# 467444_130_3_4.net
KiCad netlist of a schematic drawn in Altium Designer
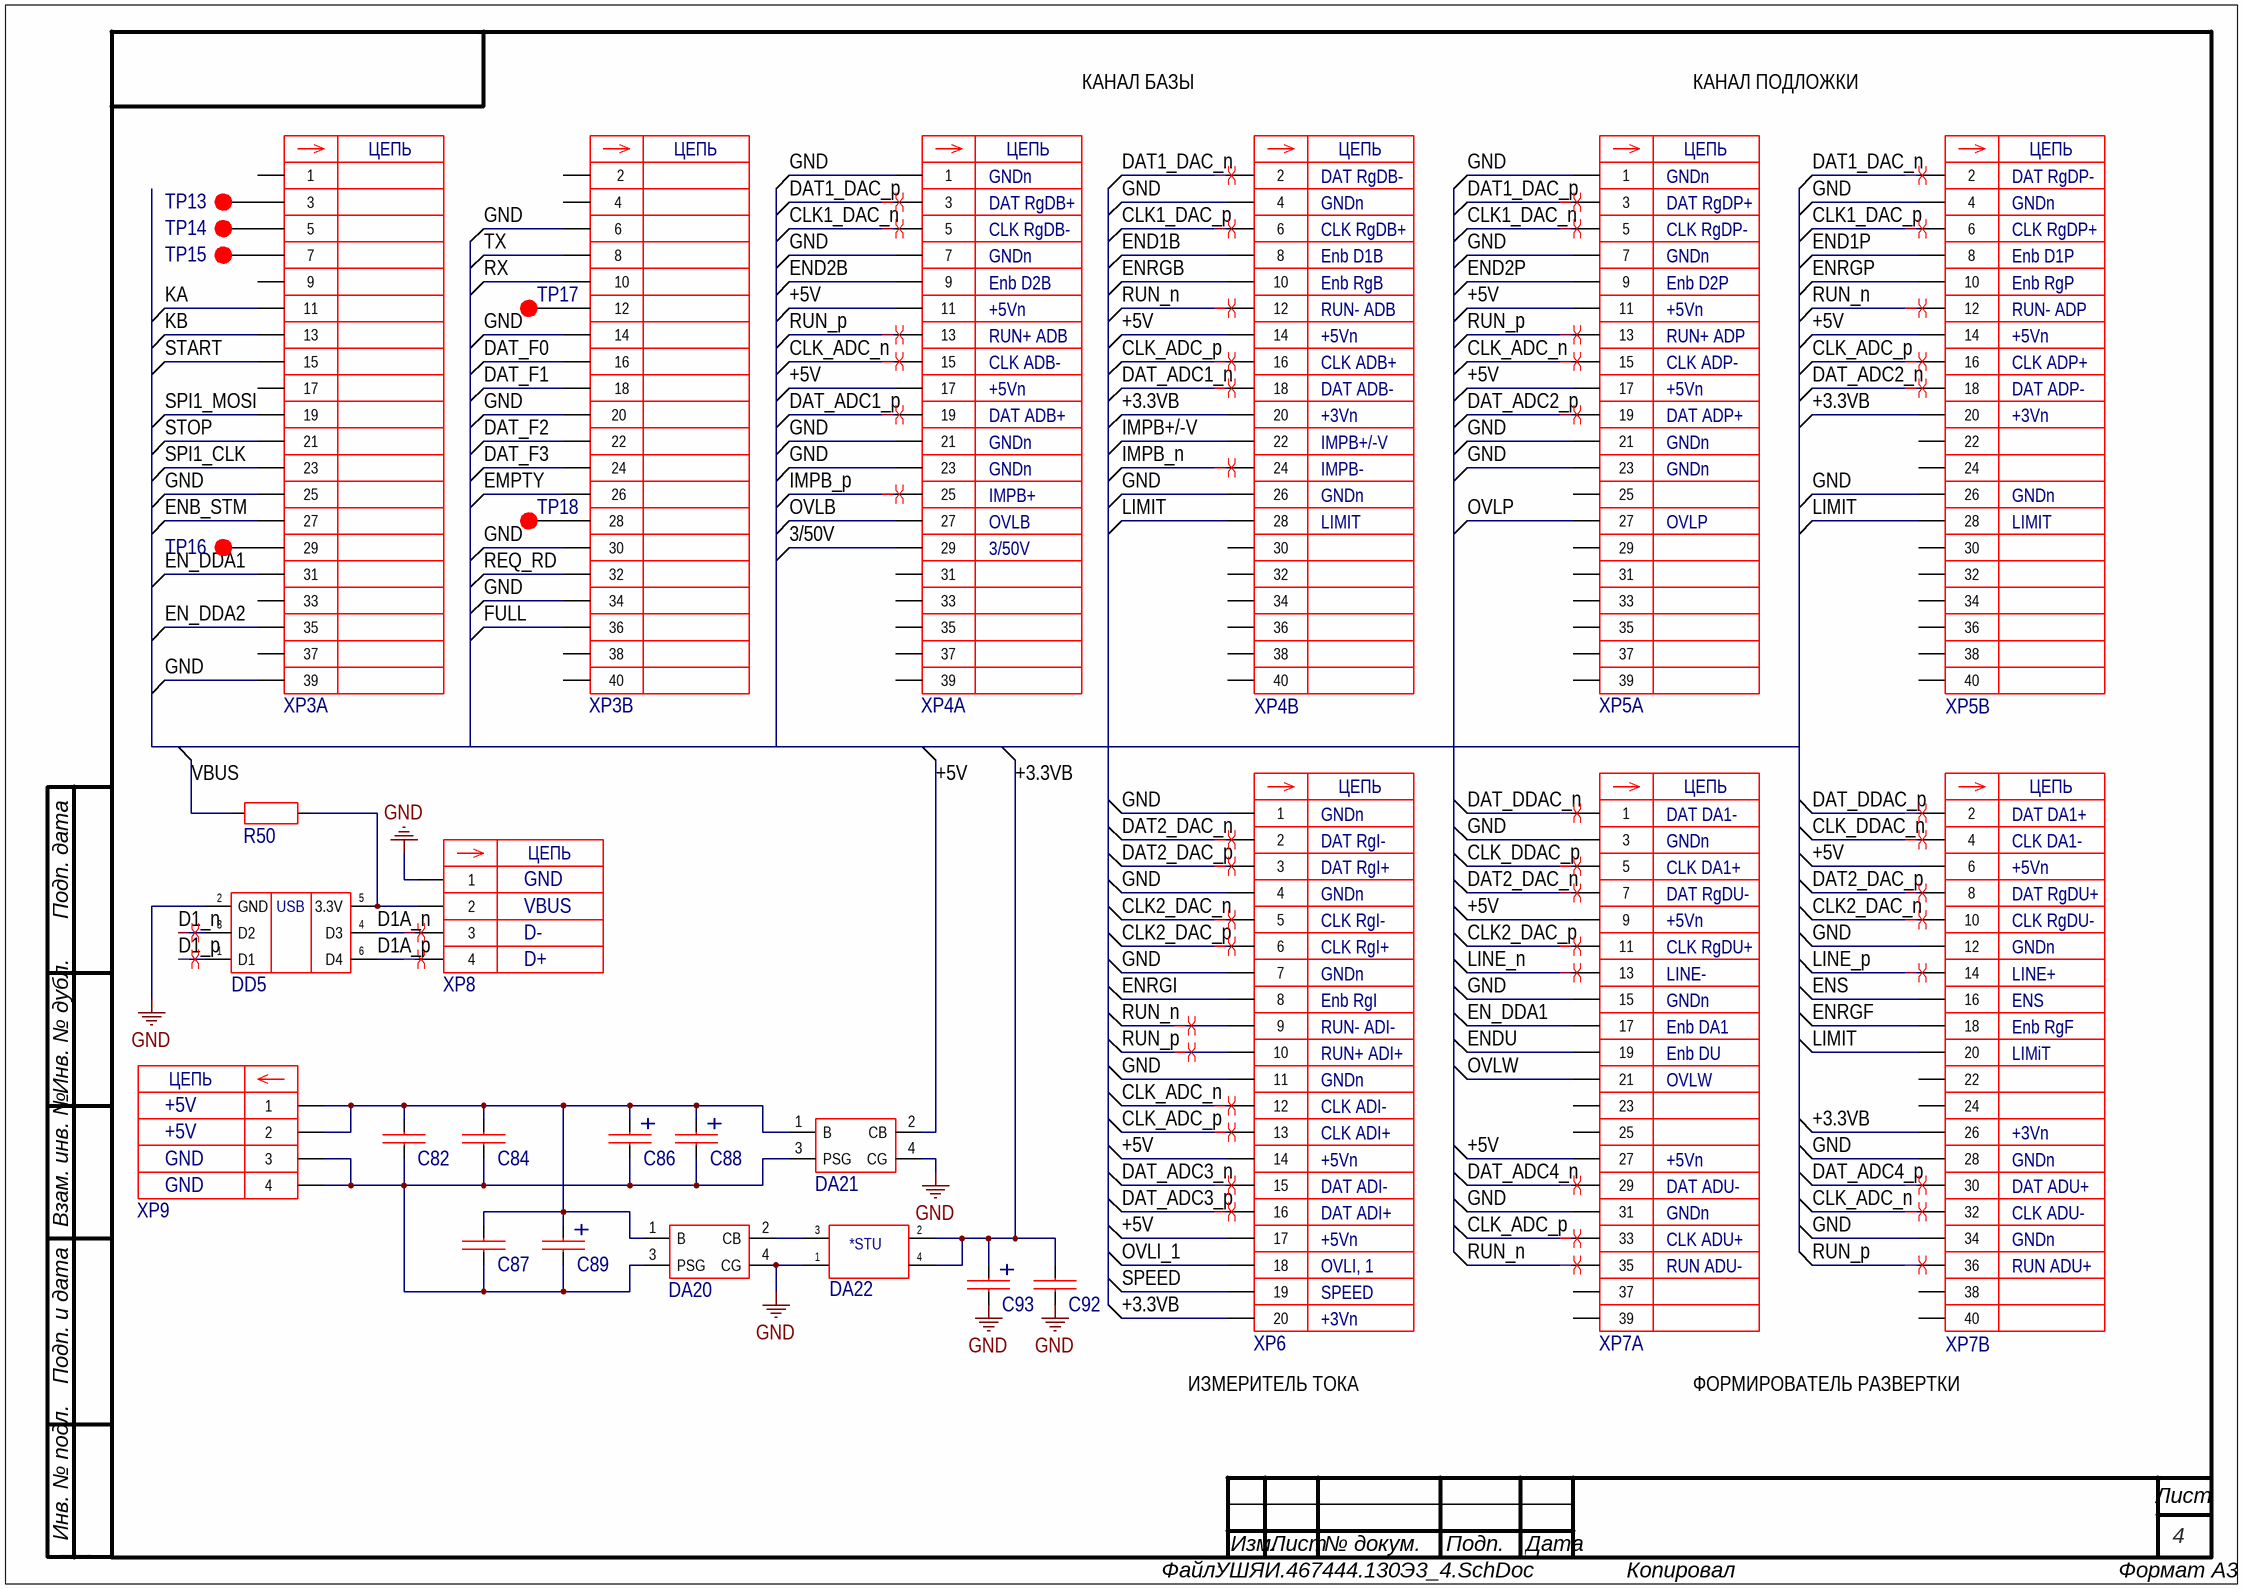
[diagram p0: УШЯИ.467444.130Э3_4.SchDoc]

(export (version "E")
  (design (tool "Eeschema 10.0.6"))
  (components
    (comp (ref "C82")
      (value "0,1 µF")
      (footprint "C_0805 [2012 Metric]")
      (description "Неполярный конденсатор")
      (fields (field (name "MANUFACTURER") "Murata") (field (name "VOLTAGE") "50V"))
      (libsource (lib "lib") (part "C_const"))
    )
    (comp (ref "C84")
      (value "0,1 µF")
      (footprint "C_0805 [2012 Metric]")
      (description "Неполярный конденсатор")
      (fields (field (name "MANUFACTURER") "Murata") (field (name "VOLTAGE") "50V"))
      (libsource (lib "lib") (part "C_const"))
    )
    (comp (ref "C86")
      (value "1000 µF")
      (footprint "С_EXR_10x21")
      (description "Полярный конденсатор")
      (fields (field (name "MANUFACTURER") "Hitano") (field (name "VOLTAGE") "16V"))
      (libsource (lib "lib") (part "C_electrolytic"))
    )
    (comp (ref "C87")
      (value "0,1 µF")
      (footprint "C_0805 [2012 Metric]")
      (description "Неполярный конденсатор")
      (fields (field (name "MANUFACTURER") "Murata") (field (name "VOLTAGE") "50V"))
      (libsource (lib "lib") (part "C_const"))
    )
    (comp (ref "C88")
      (value "10 µF")
      (footprint "C+_1210 [3528-21 Metric]")
      (description "Полярный конденсатор")
      (fields (field (name "MANUFACTURER") "KYOCERA AVX") (field (name "VOLTAGE") "20V\r\n10V"))
      (libsource (lib "lib") (part "C_electrolytic"))
    )
    (comp (ref "C89")
      (value "10 µF")
      (footprint "C+_1210 [3528-21 Metric]")
      (description "Полярный конденсатор")
      (fields (field (name "MANUFACTURER") "KYOCERA AVX") (field (name "VOLTAGE") "20V\r\n10V"))
      (libsource (lib "lib") (part "C_electrolytic"))
    )
    (comp (ref "C92")
      (value "0,1 µF")
      (footprint "C_0805 [2012 Metric]")
      (description "Неполярный конденсатор")
      (fields (field (name "MANUFACTURER") "Murata") (field (name "VOLTAGE") "50V"))
      (libsource (lib "lib") (part "C_const"))
    )
    (comp (ref "C93")
      (value "10 µF")
      (footprint "C+_1210 [3528-21 Metric]")
      (description "Полярный конденсатор")
      (fields (field (name "MANUFACTURER") "KYOCERA AVX") (field (name "VOLTAGE") "20V\r\n10V"))
      (libsource (lib "lib") (part "C_electrolytic"))
    )
    (comp (ref "DA20")
      (value "BNX028-01")
      (footprint "F_BNX028-01")
      (description "16В, 35дБ")
      (fields (field (name "MANUFACTURER") "Murata Electronics"))
      (libsource (lib "lib") (part "F_BNX022-01"))
    )
    (comp (ref "DA21")
      (value "BNX028-01")
      (footprint "F_BNX028-01")
      (description "16В, 35дБ")
      (fields (field (name "MANUFACTURER") "Murata Electronics"))
      (libsource (lib "lib") (part "F_BNX022-01"))
    )
    (comp (ref "DA22")
      (value "LD1117AS33TR")
      (footprint "SOT-223")
      (description "IC, Fixed LDO Voltage Regulator, 5.3V to 10V, 1.15V Dropout, 3.3Vout, 1Aout")
      (fields (field (name "MANUFACTURER") "STMicroelectronics"))
      (libsource (lib "lib") (part "VolReg_LD1117AS33TR"))
    )
    (comp (ref "DD5")
      (value "USBUF01W6")
      (footprint "SOT-323-6")
      (description "EMI Filter, 2-Channel, USB Upstream Terminator, ESD Protection")
      (fields (field (name "MANUFACTURER") "STMicroelectronics"))
      (libsource (lib "lib") (part "USBUF01W6"))
    )
    (comp (ref "R50")
      (value "30R")
      (footprint "R_0805 [2012 Metric]")
      (fields (field (name "TOLERANCE") "±5%"))
      (libsource (lib "lib") (part "R_Const"))
    )
    (comp (ref "TP13") (value "~") (footprint "DSP_1.3") (libsource (lib "lib") (part "TP")))
    (comp (ref "TP14") (value "~") (footprint "DSP_1.3") (libsource (lib "lib") (part "TP")))
    (comp (ref "TP15") (value "~") (footprint "DSP_1.3") (libsource (lib "lib") (part "TP")))
    (comp (ref "TP16") (value "~") (footprint "DSP_1.3") (libsource (lib "lib") (part "TP")))
    (comp (ref "TP17") (value "~") (footprint "DSP_1.3") (libsource (lib "lib") (part "TP")))
    (comp (ref "TP18") (value "~") (footprint "DSP_1.3") (libsource (lib "lib") (part "TP")))
    (comp (ref "XP3")
      (value "BH-40")
      (footprint "BH-40")
      (description "Male, 40 pins, 2 rows, Vertical")
      (fields (field (name "MANUFACTURER") "Connfly electronic"))
      (libsource (lib "lib") (part "M_40"))
    )
    (comp (ref "XP4")
      (value "BH2-40")
      (footprint "BH2-40")
      (description "Male, 40 pins, 2 rows, Vertical, DS1014-40, 2 mm")
      (fields (field (name "MANUFACTURER") "Connfly electronic"))
      (libsource (lib "lib") (part "M_40"))
    )
    (comp (ref "XP5")
      (value "BH2-40")
      (footprint "BH2-40")
      (description "Male, 40 pins, 2 rows, Vertical, DS1014-40, 2 mm")
      (fields (field (name "MANUFACTURER") "Connfly electronic"))
      (libsource (lib "lib") (part "M_40"))
    )
    (comp (ref "XP6")
      (value "BH2-20R")
      (footprint "BH2-20R")
      (description "Male, 20 pins, 2 rows, Right Angle, DS1014-20RF1B-B, 2 mm")
      (fields (field (name "MANUFACTURER") "Connfly electronic"))
      (libsource (lib "lib") (part "M_20"))
    )
    (comp (ref "XP7")
      (value "BH2-40")
      (footprint "BH2-40")
      (description "Male, 40 pins, 2 rows, Vertical, DS1014-40, 2 mm")
      (fields (field (name "MANUFACTURER") "Connfly electronic"))
      (libsource (lib "lib") (part "M_40"))
    )
    (comp (ref "XP8")
      (value "AMPMODU II 280371-2")
      (footprint "AMP II-280371-2")
      (description "Male, 4 pin, 1 row, Vertical, Board-to-Board, 2.54 mm")
      (fields (field (name "MANUFACTURER") "TE Connectivity"))
      (libsource (lib "") (part "M_4_1"))
    )
    (comp (ref "XP9")
      (value "AMPMODU II 280371-2")
      (footprint "AMP II-280371-2")
      (description "Male, 4 pin, 1 row, Vertical, Board-to-Board, 2.54 mm")
      (fields (field (name "MANUFACTURER") "TE Connectivity"))
      (libsource (lib "lib") (part "M_4"))
    )
  )
  (nets
    (net (code "1") (name "/+3.3VB") (class "Default")
      (node (ref "C92") (pin "2") (pinfunction "2_2") (pintype "passive"))
      (node (ref "C93") (pin "+") (pinfunction "+_+") (pintype "passive"))
      (node (ref "DA22") (pin "2") (pinfunction "VOUT_2") (pintype "passive"))
      (node (ref "DA22") (pin "4") (pinfunction "VOUT_4") (pintype "passive"))
      (node (ref "XP4") (pin "20") (pinfunction "20_20") (pintype "passive"))
      (node (ref "XP5") (pin "20") (pinfunction "20_20") (pintype "passive"))
      (node (ref "XP6") (pin "20") (pinfunction "20_20") (pintype "passive"))
      (node (ref "XP7") (pin "26") (pinfunction "26_26") (pintype "passive"))
    )
    (net (code "2") (name "/+5V") (class "Default")
      (node (ref "DA21") (pin "2") (pinfunction "CB_2") (pintype "passive"))
      (node (ref "XP4") (pin "11") (pinfunction "11_11") (pintype "passive"))
      (node (ref "XP4") (pin "14") (pinfunction "14_14") (pintype "passive"))
      (node (ref "XP4") (pin "17") (pinfunction "17_17") (pintype "passive"))
      (node (ref "XP5") (pin "11") (pinfunction "11_11") (pintype "passive"))
      (node (ref "XP5") (pin "14") (pinfunction "14_14") (pintype "passive"))
      (node (ref "XP5") (pin "17") (pinfunction "17_17") (pintype "passive"))
      (node (ref "XP6") (pin "14") (pinfunction "14_14") (pintype "passive"))
      (node (ref "XP6") (pin "17") (pinfunction "17_17") (pintype "passive"))
      (node (ref "XP7") (pin "27") (pinfunction "27_27") (pintype "passive"))
      (node (ref "XP7") (pin "6") (pinfunction "6_6") (pintype "passive"))
      (node (ref "XP7") (pin "9") (pinfunction "9_9") (pintype "passive"))
    )
    (net (code "3") (name "/3{slash}50V") (class "Default")
      (node (ref "XP4") (pin "29") (pinfunction "29_29") (pintype "passive"))
    )
    (net (code "4") (name "/CLK1_DAC_n") (class "Default")
      (node (ref "XP4") (pin "5") (pinfunction "5_5") (pintype "passive"))
      (node (ref "XP5") (pin "5") (pinfunction "5_5") (pintype "passive"))
    )
    (net (code "5") (name "/CLK1_DAC_p") (class "Default")
      (node (ref "XP4") (pin "6") (pinfunction "6_6") (pintype "passive"))
      (node (ref "XP5") (pin "6") (pinfunction "6_6") (pintype "passive"))
    )
    (net (code "6") (name "/CLK2_DAC_n") (class "Default")
      (node (ref "XP6") (pin "5") (pinfunction "5_5") (pintype "passive"))
      (node (ref "XP7") (pin "10") (pinfunction "10_10") (pintype "passive"))
    )
    (net (code "7") (name "/CLK2_DAC_p") (class "Default")
      (node (ref "XP6") (pin "6") (pinfunction "6_6") (pintype "passive"))
      (node (ref "XP7") (pin "11") (pinfunction "11_11") (pintype "passive"))
    )
    (net (code "8") (name "/CLK_ADC_n") (class "Default")
      (node (ref "XP4") (pin "15") (pinfunction "15_15") (pintype "passive"))
      (node (ref "XP5") (pin "15") (pinfunction "15_15") (pintype "passive"))
      (node (ref "XP6") (pin "12") (pinfunction "12_12") (pintype "passive"))
      (node (ref "XP7") (pin "32") (pinfunction "32_32") (pintype "passive"))
    )
    (net (code "9") (name "/CLK_ADC_p") (class "Default")
      (node (ref "XP4") (pin "16") (pinfunction "16_16") (pintype "passive"))
      (node (ref "XP5") (pin "16") (pinfunction "16_16") (pintype "passive"))
      (node (ref "XP6") (pin "13") (pinfunction "13_13") (pintype "passive"))
      (node (ref "XP7") (pin "33") (pinfunction "33_33") (pintype "passive"))
    )
    (net (code "10") (name "/CLK_DDAC_n") (class "Default")
      (node (ref "XP7") (pin "4") (pinfunction "4_4") (pintype "passive"))
    )
    (net (code "11") (name "/CLK_DDAC_p") (class "Default")
      (node (ref "XP7") (pin "5") (pinfunction "5_5") (pintype "passive"))
    )
    (net (code "12") (name "/D1A_n") (class "Default")
      (node (ref "DD5") (pin "4") (pinfunction "D3_4") (pintype "passive"))
      (node (ref "XP8") (pin "3") (pinfunction "3_3") (pintype "passive"))
    )
    (net (code "13") (name "/D1A_p") (class "Default")
      (node (ref "DD5") (pin "6") (pinfunction "D4_6") (pintype "passive"))
      (node (ref "XP8") (pin "4") (pinfunction "4_4") (pintype "passive"))
    )
    (net (code "14") (name "/D1_n") (class "Default")
      (node (ref "DD5") (pin "3") (pinfunction "D2_3") (pintype "passive"))
    )
    (net (code "15") (name "/D1_p") (class "Default")
      (node (ref "DD5") (pin "1") (pinfunction "D1_1") (pintype "passive"))
    )
    (net (code "16") (name "/DAT1_DAC_n") (class "Default")
      (node (ref "XP4") (pin "2") (pinfunction "2_2") (pintype "passive"))
      (node (ref "XP5") (pin "2") (pinfunction "2_2") (pintype "passive"))
    )
    (net (code "17") (name "/DAT1_DAC_p") (class "Default")
      (node (ref "XP4") (pin "3") (pinfunction "3_3") (pintype "passive"))
      (node (ref "XP5") (pin "3") (pinfunction "3_3") (pintype "passive"))
    )
    (net (code "18") (name "/DAT2_DAC_n") (class "Default")
      (node (ref "XP6") (pin "2") (pinfunction "2_2") (pintype "passive"))
      (node (ref "XP7") (pin "7") (pinfunction "7_7") (pintype "passive"))
    )
    (net (code "19") (name "/DAT2_DAC_p") (class "Default")
      (node (ref "XP6") (pin "3") (pinfunction "3_3") (pintype "passive"))
      (node (ref "XP7") (pin "8") (pinfunction "8_8") (pintype "passive"))
    )
    (net (code "20") (name "/DAT_ADC1_n") (class "Default")
      (node (ref "XP4") (pin "18") (pinfunction "18_18") (pintype "passive"))
    )
    (net (code "21") (name "/DAT_ADC1_p") (class "Default")
      (node (ref "XP4") (pin "19") (pinfunction "19_19") (pintype "passive"))
    )
    (net (code "22") (name "/DAT_ADC2_n") (class "Default")
      (node (ref "XP5") (pin "18") (pinfunction "18_18") (pintype "passive"))
    )
    (net (code "23") (name "/DAT_ADC2_p") (class "Default")
      (node (ref "XP5") (pin "19") (pinfunction "19_19") (pintype "passive"))
    )
    (net (code "24") (name "/DAT_ADC3_n") (class "Default")
      (node (ref "XP6") (pin "15") (pinfunction "15_15") (pintype "passive"))
    )
    (net (code "25") (name "/DAT_ADC3_p") (class "Default")
      (node (ref "XP6") (pin "16") (pinfunction "16_16") (pintype "passive"))
    )
    (net (code "26") (name "/DAT_ADC4_n") (class "Default")
      (node (ref "XP7") (pin "29") (pinfunction "29_29") (pintype "passive"))
    )
    (net (code "27") (name "/DAT_ADC4_p") (class "Default")
      (node (ref "XP7") (pin "30") (pinfunction "30_30") (pintype "passive"))
    )
    (net (code "28") (name "/DAT_DDAC_n") (class "Default")
      (node (ref "XP7") (pin "1") (pinfunction "1_1") (pintype "passive"))
    )
    (net (code "29") (name "/DAT_DDAC_p") (class "Default")
      (node (ref "XP7") (pin "2") (pinfunction "2_2") (pintype "passive"))
    )
    (net (code "30") (name "/DAT_F0") (class "Default")
      (node (ref "XP3") (pin "16") (pinfunction "16_16") (pintype "passive"))
    )
    (net (code "31") (name "/DAT_F1") (class "Default")
      (node (ref "XP3") (pin "18") (pinfunction "18_18") (pintype "passive"))
    )
    (net (code "32") (name "/DAT_F2") (class "Default")
      (node (ref "XP3") (pin "22") (pinfunction "22_22") (pintype "passive"))
    )
    (net (code "33") (name "/DAT_F3") (class "Default")
      (node (ref "XP3") (pin "24") (pinfunction "24_24") (pintype "passive"))
    )
    (net (code "34") (name "/EMPTY") (class "Default")
      (node (ref "XP3") (pin "26") (pinfunction "26_26") (pintype "passive"))
    )
    (net (code "35") (name "/ENB_STM") (class "Default")
      (node (ref "XP3") (pin "27") (pinfunction "27_27") (pintype "passive"))
    )
    (net (code "36") (name "/END1B") (class "Default")
      (node (ref "XP4") (pin "8") (pinfunction "8_8") (pintype "passive"))
    )
    (net (code "37") (name "/END1P") (class "Default")
      (node (ref "XP5") (pin "8") (pinfunction "8_8") (pintype "passive"))
    )
    (net (code "38") (name "/END2B") (class "Default")
      (node (ref "XP4") (pin "9") (pinfunction "9_9") (pintype "passive"))
    )
    (net (code "39") (name "/END2P") (class "Default")
      (node (ref "XP5") (pin "9") (pinfunction "9_9") (pintype "passive"))
    )
    (net (code "40") (name "/ENDU") (class "Default")
      (node (ref "XP7") (pin "19") (pinfunction "19_19") (pintype "passive"))
    )
    (net (code "41") (name "/ENRGB") (class "Default")
      (node (ref "XP4") (pin "10") (pinfunction "10_10") (pintype "passive"))
    )
    (net (code "42") (name "/ENRGF") (class "Default")
      (node (ref "XP7") (pin "18") (pinfunction "18_18") (pintype "passive"))
    )
    (net (code "43") (name "/ENRGI") (class "Default")
      (node (ref "XP6") (pin "8") (pinfunction "8_8") (pintype "passive"))
    )
    (net (code "44") (name "/ENRGP") (class "Default")
      (node (ref "XP5") (pin "10") (pinfunction "10_10") (pintype "passive"))
    )
    (net (code "45") (name "/ENS") (class "Default")
      (node (ref "XP7") (pin "16") (pinfunction "16_16") (pintype "passive"))
    )
    (net (code "46") (name "/EN_DDA1") (class "Default")
      (node (ref "XP3") (pin "31") (pinfunction "31_31") (pintype "passive"))
      (node (ref "XP7") (pin "17") (pinfunction "17_17") (pintype "passive"))
    )
    (net (code "47") (name "/EN_DDA2") (class "Default")
      (node (ref "XP3") (pin "35") (pinfunction "35_35") (pintype "passive"))
    )
    (net (code "48") (name "/FULL") (class "Default")
      (node (ref "XP3") (pin "36") (pinfunction "36_36") (pintype "passive"))
    )
    (net (code "49") (name "/IMPB+{slash}-V") (class "Default")
      (node (ref "XP4") (pin "22") (pinfunction "22_22") (pintype "passive"))
    )
    (net (code "50") (name "/IMPB_n") (class "Default")
      (node (ref "XP4") (pin "24") (pinfunction "24_24") (pintype "passive"))
    )
    (net (code "51") (name "/IMPB_p") (class "Default")
      (node (ref "XP4") (pin "25") (pinfunction "25_25") (pintype "passive"))
    )
    (net (code "52") (name "/KA") (class "Default")
      (node (ref "XP3") (pin "11") (pinfunction "11_11") (pintype "passive"))
    )
    (net (code "53") (name "/KB") (class "Default")
      (node (ref "XP3") (pin "13") (pinfunction "13_13") (pintype "passive"))
    )
    (net (code "54") (name "/LIMIT") (class "Default")
      (node (ref "XP4") (pin "28") (pinfunction "28_28") (pintype "passive"))
      (node (ref "XP5") (pin "28") (pinfunction "28_28") (pintype "passive"))
      (node (ref "XP7") (pin "20") (pinfunction "20_20") (pintype "passive"))
    )
    (net (code "55") (name "/LINE_n") (class "Default")
      (node (ref "XP7") (pin "13") (pinfunction "13_13") (pintype "passive"))
    )
    (net (code "56") (name "/LINE_p") (class "Default")
      (node (ref "XP7") (pin "14") (pinfunction "14_14") (pintype "passive"))
    )
    (net (code "57") (name "/OVLB") (class "Default")
      (node (ref "XP4") (pin "27") (pinfunction "27_27") (pintype "passive"))
    )
    (net (code "58") (name "/OVLI_1") (class "Default")
      (node (ref "XP6") (pin "18") (pinfunction "18_18") (pintype "passive"))
    )
    (net (code "59") (name "/OVLP") (class "Default")
      (node (ref "XP5") (pin "27") (pinfunction "27_27") (pintype "passive"))
    )
    (net (code "60") (name "/OVLW") (class "Default")
      (node (ref "XP7") (pin "21") (pinfunction "21_21") (pintype "passive"))
    )
    (net (code "61") (name "/REQ_RD") (class "Default")
      (node (ref "XP3") (pin "32") (pinfunction "32_32") (pintype "passive"))
    )
    (net (code "62") (name "/RUN_n") (class "Default")
      (node (ref "XP4") (pin "12") (pinfunction "12_12") (pintype "passive"))
      (node (ref "XP5") (pin "12") (pinfunction "12_12") (pintype "passive"))
      (node (ref "XP6") (pin "9") (pinfunction "9_9") (pintype "passive"))
      (node (ref "XP7") (pin "35") (pinfunction "35_35") (pintype "passive"))
    )
    (net (code "63") (name "/RUN_p") (class "Default")
      (node (ref "XP4") (pin "13") (pinfunction "13_13") (pintype "passive"))
      (node (ref "XP5") (pin "13") (pinfunction "13_13") (pintype "passive"))
      (node (ref "XP6") (pin "10") (pinfunction "10_10") (pintype "passive"))
      (node (ref "XP7") (pin "36") (pinfunction "36_36") (pintype "passive"))
    )
    (net (code "64") (name "/RX") (class "Default")
      (node (ref "XP3") (pin "10") (pinfunction "10_10") (pintype "passive"))
    )
    (net (code "65") (name "/SPEED") (class "Default")
      (node (ref "XP6") (pin "19") (pinfunction "19_19") (pintype "passive"))
    )
    (net (code "66") (name "/SPI1_CLK") (class "Default")
      (node (ref "XP3") (pin "23") (pinfunction "23_23") (pintype "passive"))
    )
    (net (code "67") (name "/SPI1_MOSI") (class "Default")
      (node (ref "XP3") (pin "19") (pinfunction "19_19") (pintype "passive"))
    )
    (net (code "68") (name "/START") (class "Default")
      (node (ref "XP3") (pin "15") (pinfunction "15_15") (pintype "passive"))
    )
    (net (code "69") (name "/STOP") (class "Default")
      (node (ref "XP3") (pin "21") (pinfunction "21_21") (pintype "passive"))
    )
    (net (code "70") (name "/TX") (class "Default")
      (node (ref "XP3") (pin "8") (pinfunction "8_8") (pintype "passive"))
    )
    (net (code "71") (name "/VBUS") (class "Default")
      (node (ref "R50") (pin "1") (pinfunction "1_1") (pintype "passive"))
    )
    (net (code "72") (name "GND") (class "Default")
      (node (ref "C92") (pin "1") (pinfunction "1_1") (pintype "passive"))
      (node (ref "C93") (pin "-") (pinfunction "-_-") (pintype "passive"))
      (node (ref "DA20") (pin "4") (pinfunction "CG_4") (pintype "passive"))
      (node (ref "DA21") (pin "4") (pinfunction "CG_4") (pintype "passive"))
      (node (ref "DA22") (pin "1") (pinfunction "ADJ/GND_1") (pintype "passive"))
      (node (ref "DD5") (pin "2") (pinfunction "GND_2") (pintype "passive"))
      (node (ref "XP3") (pin "14") (pinfunction "14_14") (pintype "passive"))
      (node (ref "XP3") (pin "20") (pinfunction "20_20") (pintype "passive"))
      (node (ref "XP3") (pin "25") (pinfunction "25_25") (pintype "passive"))
      (node (ref "XP3") (pin "30") (pinfunction "30_30") (pintype "passive"))
      (node (ref "XP3") (pin "34") (pinfunction "34_34") (pintype "passive"))
      (node (ref "XP3") (pin "39") (pinfunction "39_39") (pintype "passive"))
      (node (ref "XP3") (pin "6") (pinfunction "6_6") (pintype "passive"))
      (node (ref "XP4") (pin "1") (pinfunction "1_1") (pintype "passive"))
      (node (ref "XP4") (pin "21") (pinfunction "21_21") (pintype "passive"))
      (node (ref "XP4") (pin "23") (pinfunction "23_23") (pintype "passive"))
      (node (ref "XP4") (pin "26") (pinfunction "26_26") (pintype "passive"))
      (node (ref "XP4") (pin "4") (pinfunction "4_4") (pintype "passive"))
      (node (ref "XP4") (pin "7") (pinfunction "7_7") (pintype "passive"))
      (node (ref "XP5") (pin "1") (pinfunction "1_1") (pintype "passive"))
      (node (ref "XP5") (pin "21") (pinfunction "21_21") (pintype "passive"))
      (node (ref "XP5") (pin "23") (pinfunction "23_23") (pintype "passive"))
      (node (ref "XP5") (pin "26") (pinfunction "26_26") (pintype "passive"))
      (node (ref "XP5") (pin "4") (pinfunction "4_4") (pintype "passive"))
      (node (ref "XP5") (pin "7") (pinfunction "7_7") (pintype "passive"))
      (node (ref "XP6") (pin "1") (pinfunction "1_1") (pintype "passive"))
      (node (ref "XP6") (pin "11") (pinfunction "11_11") (pintype "passive"))
      (node (ref "XP6") (pin "4") (pinfunction "4_4") (pintype "passive"))
      (node (ref "XP6") (pin "7") (pinfunction "7_7") (pintype "passive"))
      (node (ref "XP7") (pin "12") (pinfunction "12_12") (pintype "passive"))
      (node (ref "XP7") (pin "15") (pinfunction "15_15") (pintype "passive"))
      (node (ref "XP7") (pin "28") (pinfunction "28_28") (pintype "passive"))
      (node (ref "XP7") (pin "3") (pinfunction "3_3") (pintype "passive"))
      (node (ref "XP7") (pin "31") (pinfunction "31_31") (pintype "passive"))
      (node (ref "XP7") (pin "34") (pinfunction "34_34") (pintype "passive"))
      (node (ref "XP8") (pin "1") (pinfunction "1_1") (pintype "passive"))
    )
    (net (code "73") (name "Net-(DA20-B)") (class "Default")
      (node (ref "C82") (pin "1") (pinfunction "1_1") (pintype "passive"))
      (node (ref "C84") (pin "1") (pinfunction "1_1") (pintype "passive"))
      (node (ref "C86") (pin "+") (pinfunction "+_+") (pintype "passive"))
      (node (ref "C87") (pin "2") (pinfunction "2_2") (pintype "passive"))
      (node (ref "C88") (pin "+") (pinfunction "+_+") (pintype "passive"))
      (node (ref "C89") (pin "+") (pinfunction "+_+") (pintype "passive"))
      (node (ref "DA20") (pin "1") (pinfunction "B_1") (pintype "passive"))
      (node (ref "DA21") (pin "1") (pinfunction "B_1") (pintype "passive"))
      (node (ref "XP9") (pin "1") (pinfunction "1_1") (pintype "passive"))
      (node (ref "XP9") (pin "2") (pinfunction "2_2") (pintype "passive"))
    )
    (net (code "74") (name "Net-(DA20-CB)") (class "Default")
      (node (ref "DA20") (pin "2") (pinfunction "CB_2") (pintype "passive"))
      (node (ref "DA22") (pin "3") (pinfunction "VIN_3") (pintype "passive"))
    )
    (net (code "75") (name "Net-(DA20-PSG)") (class "Default")
      (node (ref "C82") (pin "2") (pinfunction "2_2") (pintype "passive"))
      (node (ref "C84") (pin "2") (pinfunction "2_2") (pintype "passive"))
      (node (ref "C86") (pin "-") (pinfunction "-_-") (pintype "passive"))
      (node (ref "C87") (pin "1") (pinfunction "1_1") (pintype "passive"))
      (node (ref "C88") (pin "-") (pinfunction "-_-") (pintype "passive"))
      (node (ref "C89") (pin "-") (pinfunction "-_-") (pintype "passive"))
      (node (ref "DA20") (pin "3") (pinfunction "PSG_3") (pintype "passive"))
      (node (ref "DA21") (pin "3") (pinfunction "PSG_3") (pintype "passive"))
      (node (ref "XP9") (pin "3") (pinfunction "3_3") (pintype "passive"))
      (node (ref "XP9") (pin "4") (pinfunction "4_4") (pintype "passive"))
    )
    (net (code "76") (name "Net-(DD5-3.3V)") (class "Default")
      (node (ref "DD5") (pin "5") (pinfunction "3.3V_5") (pintype "passive"))
      (node (ref "R50") (pin "2") (pinfunction "2_2") (pintype "passive"))
      (node (ref "XP8") (pin "2") (pinfunction "2_2") (pintype "passive"))
    )
    (net (code "77") (name "Net-(TP13-Pad1)") (class "Default")
      (node (ref "TP13") (pin "1") (pinfunction "1_1") (pintype "passive"))
      (node (ref "XP3") (pin "3") (pinfunction "3_3") (pintype "passive"))
    )
    (net (code "78") (name "Net-(TP14-Pad1)") (class "Default")
      (node (ref "TP14") (pin "1") (pinfunction "1_1") (pintype "passive"))
      (node (ref "XP3") (pin "5") (pinfunction "5_5") (pintype "passive"))
    )
    (net (code "79") (name "Net-(TP15-Pad1)") (class "Default")
      (node (ref "TP15") (pin "1") (pinfunction "1_1") (pintype "passive"))
      (node (ref "XP3") (pin "7") (pinfunction "7_7") (pintype "passive"))
    )
    (net (code "80") (name "Net-(TP16-Pad1)") (class "Default")
      (node (ref "TP16") (pin "1") (pinfunction "1_1") (pintype "passive"))
      (node (ref "XP3") (pin "29") (pinfunction "29_29") (pintype "passive"))
    )
    (net (code "81") (name "Net-(TP17-Pad1)") (class "Default")
      (node (ref "TP17") (pin "1") (pinfunction "1_1") (pintype "passive"))
      (node (ref "XP3") (pin "12") (pinfunction "12_12") (pintype "passive"))
    )
    (net (code "82") (name "Net-(TP18-Pad1)") (class "Default")
      (node (ref "TP18") (pin "1") (pinfunction "1_1") (pintype "passive"))
      (node (ref "XP3") (pin "28") (pinfunction "28_28") (pintype "passive"))
    )
    (net (code "83") (name "unconnected-(XP3-Pad1)") (class "Default")
      (node (ref "XP3") (pin "1") (pinfunction "1_1") (pintype "passive"))
    )
    (net (code "84") (name "unconnected-(XP3-Pad2)") (class "Default")
      (node (ref "XP3") (pin "2") (pinfunction "2_2") (pintype "passive"))
    )
    (net (code "85") (name "unconnected-(XP3-Pad4)") (class "Default")
      (node (ref "XP3") (pin "4") (pinfunction "4_4") (pintype "passive"))
    )
    (net (code "86") (name "unconnected-(XP3-Pad9)") (class "Default")
      (node (ref "XP3") (pin "9") (pinfunction "9_9") (pintype "passive"))
    )
    (net (code "87") (name "unconnected-(XP3-Pad17)") (class "Default")
      (node (ref "XP3") (pin "17") (pinfunction "17_17") (pintype "passive"))
    )
    (net (code "88") (name "unconnected-(XP3-Pad33)") (class "Default")
      (node (ref "XP3") (pin "33") (pinfunction "33_33") (pintype "passive"))
    )
    (net (code "89") (name "unconnected-(XP3-Pad37)") (class "Default")
      (node (ref "XP3") (pin "37") (pinfunction "37_37") (pintype "passive"))
    )
    (net (code "90") (name "unconnected-(XP3-Pad38)") (class "Default")
      (node (ref "XP3") (pin "38") (pinfunction "38_38") (pintype "passive"))
    )
    (net (code "91") (name "unconnected-(XP3-Pad40)") (class "Default")
      (node (ref "XP3") (pin "40") (pinfunction "40_40") (pintype "passive"))
    )
    (net (code "92") (name "unconnected-(XP4-Pad30)") (class "Default")
      (node (ref "XP4") (pin "30") (pinfunction "30_30") (pintype "passive"))
    )
    (net (code "93") (name "unconnected-(XP4-Pad31)") (class "Default")
      (node (ref "XP4") (pin "31") (pinfunction "31_31") (pintype "passive"))
    )
    (net (code "94") (name "unconnected-(XP4-Pad32)") (class "Default")
      (node (ref "XP4") (pin "32") (pinfunction "32_32") (pintype "passive"))
    )
    (net (code "95") (name "unconnected-(XP4-Pad33)") (class "Default")
      (node (ref "XP4") (pin "33") (pinfunction "33_33") (pintype "passive"))
    )
    (net (code "96") (name "unconnected-(XP4-Pad34)") (class "Default")
      (node (ref "XP4") (pin "34") (pinfunction "34_34") (pintype "passive"))
    )
    (net (code "97") (name "unconnected-(XP4-Pad35)") (class "Default")
      (node (ref "XP4") (pin "35") (pinfunction "35_35") (pintype "passive"))
    )
    (net (code "98") (name "unconnected-(XP4-Pad36)") (class "Default")
      (node (ref "XP4") (pin "36") (pinfunction "36_36") (pintype "passive"))
    )
    (net (code "99") (name "unconnected-(XP4-Pad37)") (class "Default")
      (node (ref "XP4") (pin "37") (pinfunction "37_37") (pintype "passive"))
    )
    (net (code "100") (name "unconnected-(XP4-Pad38)") (class "Default")
      (node (ref "XP4") (pin "38") (pinfunction "38_38") (pintype "passive"))
    )
    (net (code "101") (name "unconnected-(XP4-Pad39)") (class "Default")
      (node (ref "XP4") (pin "39") (pinfunction "39_39") (pintype "passive"))
    )
    (net (code "102") (name "unconnected-(XP4-Pad40)") (class "Default")
      (node (ref "XP4") (pin "40") (pinfunction "40_40") (pintype "passive"))
    )
    (net (code "103") (name "unconnected-(XP5-Pad22)") (class "Default")
      (node (ref "XP5") (pin "22") (pinfunction "22_22") (pintype "passive"))
    )
    (net (code "104") (name "unconnected-(XP5-Pad24)") (class "Default")
      (node (ref "XP5") (pin "24") (pinfunction "24_24") (pintype "passive"))
    )
    (net (code "105") (name "unconnected-(XP5-Pad25)") (class "Default")
      (node (ref "XP5") (pin "25") (pinfunction "25_25") (pintype "passive"))
    )
    (net (code "106") (name "unconnected-(XP5-Pad29)") (class "Default")
      (node (ref "XP5") (pin "29") (pinfunction "29_29") (pintype "passive"))
    )
    (net (code "107") (name "unconnected-(XP5-Pad30)") (class "Default")
      (node (ref "XP5") (pin "30") (pinfunction "30_30") (pintype "passive"))
    )
    (net (code "108") (name "unconnected-(XP5-Pad31)") (class "Default")
      (node (ref "XP5") (pin "31") (pinfunction "31_31") (pintype "passive"))
    )
    (net (code "109") (name "unconnected-(XP5-Pad32)") (class "Default")
      (node (ref "XP5") (pin "32") (pinfunction "32_32") (pintype "passive"))
    )
    (net (code "110") (name "unconnected-(XP5-Pad33)") (class "Default")
      (node (ref "XP5") (pin "33") (pinfunction "33_33") (pintype "passive"))
    )
    (net (code "111") (name "unconnected-(XP5-Pad34)") (class "Default")
      (node (ref "XP5") (pin "34") (pinfunction "34_34") (pintype "passive"))
    )
    (net (code "112") (name "unconnected-(XP5-Pad35)") (class "Default")
      (node (ref "XP5") (pin "35") (pinfunction "35_35") (pintype "passive"))
    )
    (net (code "113") (name "unconnected-(XP5-Pad36)") (class "Default")
      (node (ref "XP5") (pin "36") (pinfunction "36_36") (pintype "passive"))
    )
    (net (code "114") (name "unconnected-(XP5-Pad37)") (class "Default")
      (node (ref "XP5") (pin "37") (pinfunction "37_37") (pintype "passive"))
    )
    (net (code "115") (name "unconnected-(XP5-Pad38)") (class "Default")
      (node (ref "XP5") (pin "38") (pinfunction "38_38") (pintype "passive"))
    )
    (net (code "116") (name "unconnected-(XP5-Pad39)") (class "Default")
      (node (ref "XP5") (pin "39") (pinfunction "39_39") (pintype "passive"))
    )
    (net (code "117") (name "unconnected-(XP5-Pad40)") (class "Default")
      (node (ref "XP5") (pin "40") (pinfunction "40_40") (pintype "passive"))
    )
    (net (code "118") (name "unconnected-(XP7-Pad22)") (class "Default")
      (node (ref "XP7") (pin "22") (pinfunction "22_22") (pintype "passive"))
    )
    (net (code "119") (name "unconnected-(XP7-Pad23)") (class "Default")
      (node (ref "XP7") (pin "23") (pinfunction "23_23") (pintype "passive"))
    )
    (net (code "120") (name "unconnected-(XP7-Pad24)") (class "Default")
      (node (ref "XP7") (pin "24") (pinfunction "24_24") (pintype "passive"))
    )
    (net (code "121") (name "unconnected-(XP7-Pad25)") (class "Default")
      (node (ref "XP7") (pin "25") (pinfunction "25_25") (pintype "passive"))
    )
    (net (code "122") (name "unconnected-(XP7-Pad37)") (class "Default")
      (node (ref "XP7") (pin "37") (pinfunction "37_37") (pintype "passive"))
    )
    (net (code "123") (name "unconnected-(XP7-Pad38)") (class "Default")
      (node (ref "XP7") (pin "38") (pinfunction "38_38") (pintype "passive"))
    )
    (net (code "124") (name "unconnected-(XP7-Pad39)") (class "Default")
      (node (ref "XP7") (pin "39") (pinfunction "39_39") (pintype "passive"))
    )
    (net (code "125") (name "unconnected-(XP7-Pad40)") (class "Default")
      (node (ref "XP7") (pin "40") (pinfunction "40_40") (pintype "passive"))
    )
  )
)
